# EFR32_IO.net
KiCad netlist of a schematic drawn in Altium Designer
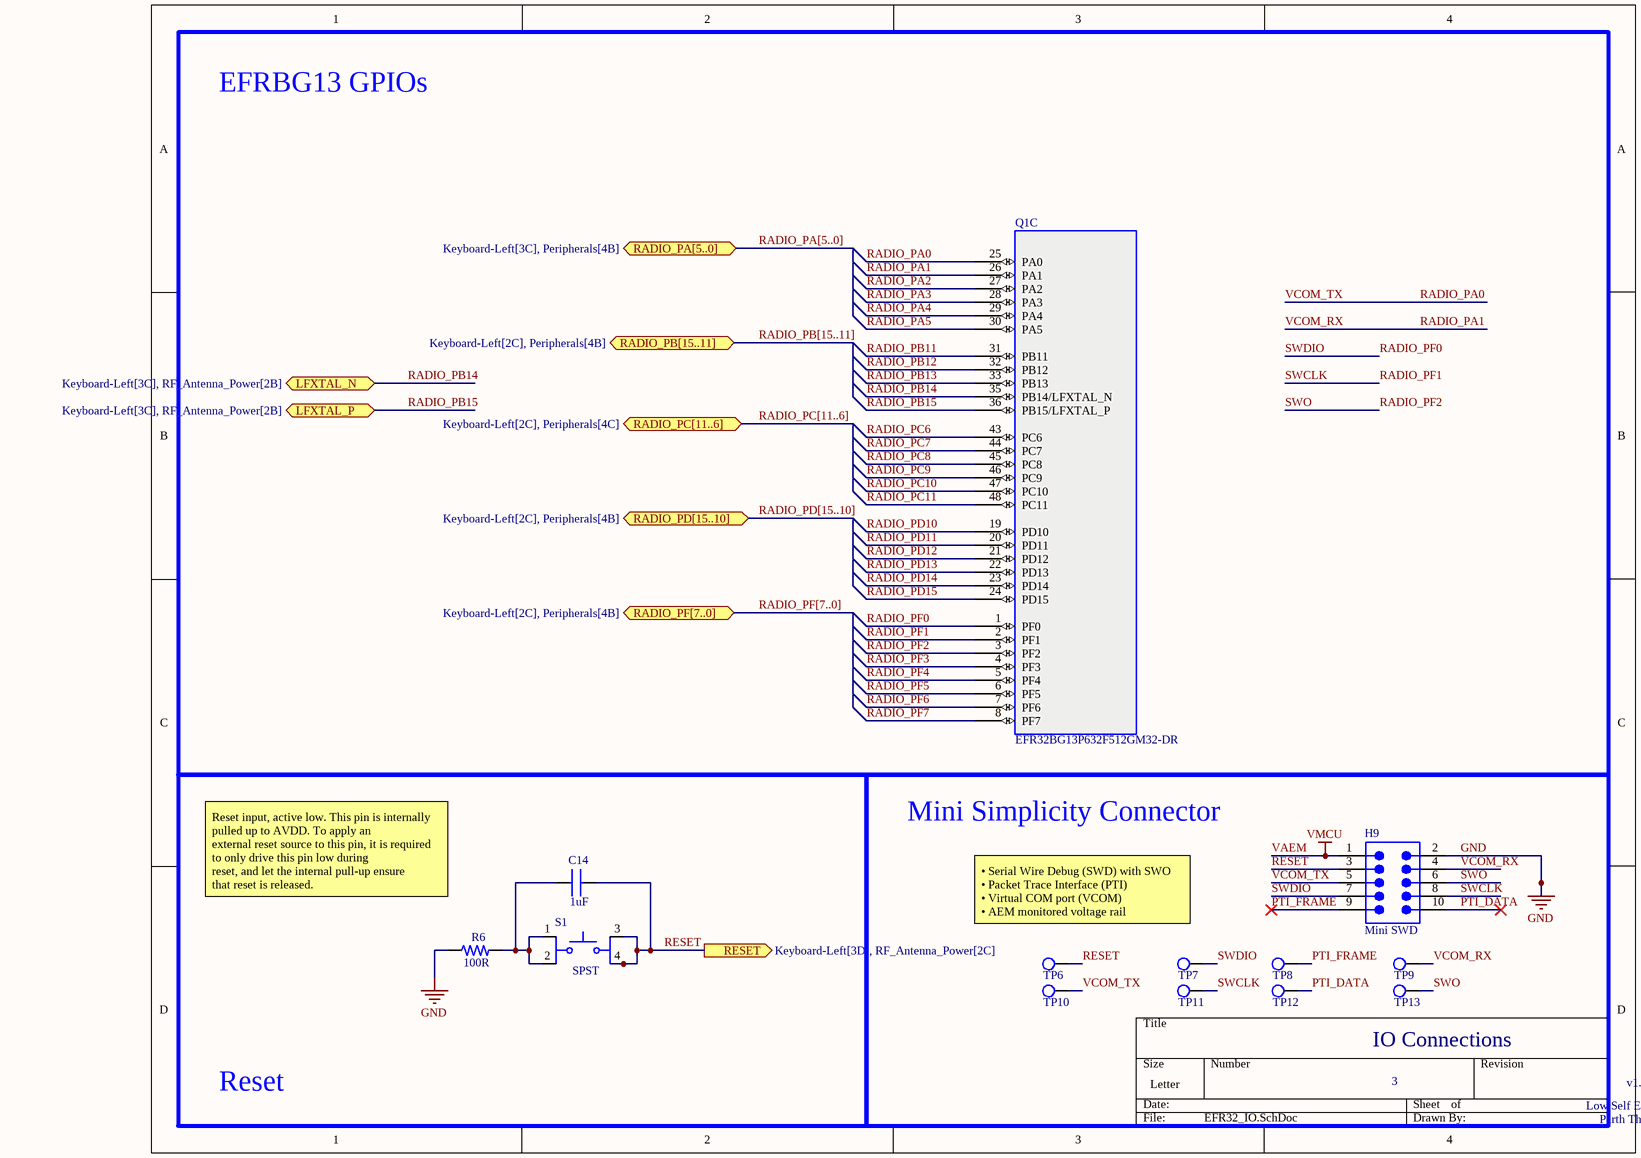
[diagram p0: EFR32_IO.SchDoc]

(export (version "E")
  (design (tool "Eeschema 10.0.6"))
  (components
    (comp (ref "C14")
      (value "1uF")
      (footprint "Capacitor 0603")
      (fields
        (field (name "MANUFACTURER") "Murata")
        (field (name "MANUFACTURER PART NUMBER") "GRM188R61A105KA61D")
        (field (name "Comment") "CAP 1uF 10V 0603")
      )
      (libsource (lib "Keyboard_parts") (part "CAP 1uF 10V 0603"))
    )
    (comp (ref "H9")
      (value "Mini SWD")
      (footprint "Mini Simplicity Connector")
      (description "Mini SWD 0.05\" Pitch Connector - 10 Pin SMT Box Header")
      (fields
        (field (name "MANUFACTURER") "Adafruit Industries")
        (field (name "MANUFACTURER PART NUMBER") "4048")
      )
      (libsource (lib "Keyboard_parts") (part "Debug Connector Mini SWD - 0.05{dblquote}"))
    )
    (comp (ref "Q1")
      (value "EFR32BG13P632F512GM32-DR")
      (footprint "EFR32BG")
      (description "BLue Gecko")
      (fields (field (name "MANUFACTURER") "Silicon Labs"))
      (libsource (lib "Keyboard_parts") (part "EFR32BG13P632F512GM32-DR"))
    )
    (comp (ref "R6")
      (value "100R")
      (footprint "Resistor 0603")
      (fields
        (field (name "MANUFACTURER") "Yageo")
        (field (name "MANUFACTURER PART NUMBER") "RC0603FR-07100RL")
        (field (name "TOLERANCE") "1%")
      )
      (libsource (lib "Keyboard_parts") (part "RES 100R 0603"))
    )
    (comp (ref "S1")
      (value "SPST")
      (footprint "SPST")
      (fields
        (field (name "MANUFACTURER") "E-Switch")
        (field (name "MANUFACTURER PART NUMBER") "TL3301NF260QG")
      )
      (libsource (lib "Keyboard_parts") (part "SPST"))
    )
    (comp (ref "TP6")
      (value "Test point")
      (footprint "Test Point")
      (libsource (lib "Keyboard_parts") (part "Test point"))
    )
    (comp (ref "TP7")
      (value "Test point")
      (footprint "Test Point")
      (libsource (lib "Keyboard_parts") (part "Test point"))
    )
    (comp (ref "TP8")
      (value "Test point")
      (footprint "Test Point")
      (libsource (lib "Keyboard_parts") (part "Test point"))
    )
    (comp (ref "TP9")
      (value "Test point")
      (footprint "Test Point")
      (libsource (lib "Keyboard_parts") (part "Test point"))
    )
    (comp (ref "TP10")
      (value "Test point")
      (footprint "Test Point")
      (libsource (lib "Keyboard_parts") (part "Test point"))
    )
    (comp (ref "TP11")
      (value "Test point")
      (footprint "Test Point")
      (libsource (lib "Keyboard_parts") (part "Test point"))
    )
    (comp (ref "TP12")
      (value "Test point")
      (footprint "Test Point")
      (libsource (lib "Keyboard_parts") (part "Test point"))
    )
    (comp (ref "TP13")
      (value "Test point")
      (footprint "Test Point")
      (libsource (lib "Keyboard_parts") (part "Test point"))
    )
  )
  (nets
    (net (code "1") (name "/PTI_DATA") (class "Default")
      (node (ref "H9") (pin "10") (pinfunction "10_10") (pintype "passive"))
      (node (ref "TP12") (pin "1") (pinfunction "1_1") (pintype "passive"))
    )
    (net (code "2") (name "/PTI_FRAME") (class "Default")
      (node (ref "H9") (pin "9") (pinfunction "9_9") (pintype "passive"))
      (node (ref "TP8") (pin "1") (pinfunction "1_1") (pintype "passive"))
    )
    (net (code "3") (name "/RADIO_PA0") (class "Default")
      (node (ref "H9") (pin "5") (pinfunction "5_5") (pintype "passive"))
      (node (ref "Q1") (pin "25") (pinfunction "PA0_25") (pintype "bidirectional"))
      (node (ref "TP10") (pin "1") (pinfunction "1_1") (pintype "passive"))
    )
    (net (code "4") (name "/RADIO_PA1") (class "Default")
      (node (ref "H9") (pin "4") (pinfunction "4_4") (pintype "passive"))
      (node (ref "Q1") (pin "26") (pinfunction "PA1_26") (pintype "bidirectional"))
      (node (ref "TP9") (pin "1") (pinfunction "1_1") (pintype "passive"))
    )
    (net (code "5") (name "/RADIO_PA2") (class "Default")
      (node (ref "Q1") (pin "27") (pinfunction "PA2_27") (pintype "bidirectional"))
    )
    (net (code "6") (name "/RADIO_PA3") (class "Default")
      (node (ref "Q1") (pin "28") (pinfunction "PA3_28") (pintype "bidirectional"))
    )
    (net (code "7") (name "/RADIO_PA4") (class "Default")
      (node (ref "Q1") (pin "29") (pinfunction "PA4_29") (pintype "bidirectional"))
    )
    (net (code "8") (name "/RADIO_PA5") (class "Default")
      (node (ref "Q1") (pin "30") (pinfunction "PA5_30") (pintype "bidirectional"))
    )
    (net (code "10") (name "/RADIO_PB11") (class "Default")
      (node (ref "Q1") (pin "31") (pinfunction "PB11_31") (pintype "bidirectional"))
    )
    (net (code "11") (name "/RADIO_PB12") (class "Default")
      (node (ref "Q1") (pin "32") (pinfunction "PB12_32") (pintype "bidirectional"))
    )
    (net (code "12") (name "/RADIO_PB13") (class "Default")
      (node (ref "Q1") (pin "33") (pinfunction "PB13_33") (pintype "bidirectional"))
    )
    (net (code "13") (name "/RADIO_PB14") (class "Default")
      (node (ref "Q1") (pin "35") (pinfunction "PB14/LFXTAL_N_35") (pintype "bidirectional"))
    )
    (net (code "14") (name "/RADIO_PB15") (class "Default")
      (node (ref "Q1") (pin "36") (pinfunction "PB15/LFXTAL_P_36") (pintype "bidirectional"))
    )
    (net (code "16") (name "/RADIO_PC6") (class "Default")
      (node (ref "Q1") (pin "43") (pinfunction "PC6_43") (pintype "bidirectional"))
    )
    (net (code "17") (name "/RADIO_PC7") (class "Default")
      (node (ref "Q1") (pin "44") (pinfunction "PC7_44") (pintype "bidirectional"))
    )
    (net (code "18") (name "/RADIO_PC8") (class "Default")
      (node (ref "Q1") (pin "45") (pinfunction "PC8_45") (pintype "bidirectional"))
    )
    (net (code "19") (name "/RADIO_PC9") (class "Default")
      (node (ref "Q1") (pin "46") (pinfunction "PC9_46") (pintype "bidirectional"))
    )
    (net (code "20") (name "/RADIO_PC10") (class "Default")
      (node (ref "Q1") (pin "47") (pinfunction "PC10_47") (pintype "bidirectional"))
    )
    (net (code "21") (name "/RADIO_PC11") (class "Default")
      (node (ref "Q1") (pin "48") (pinfunction "PC11_48") (pintype "bidirectional"))
    )
    (net (code "23") (name "/RADIO_PD10") (class "Default")
      (node (ref "Q1") (pin "19") (pinfunction "PD10_19") (pintype "bidirectional"))
    )
    (net (code "24") (name "/RADIO_PD11") (class "Default")
      (node (ref "Q1") (pin "20") (pinfunction "PD11_20") (pintype "bidirectional"))
    )
    (net (code "25") (name "/RADIO_PD12") (class "Default")
      (node (ref "Q1") (pin "21") (pinfunction "PD12_21") (pintype "bidirectional"))
    )
    (net (code "26") (name "/RADIO_PD13") (class "Default")
      (node (ref "Q1") (pin "22") (pinfunction "PD13_22") (pintype "bidirectional"))
    )
    (net (code "27") (name "/RADIO_PD14") (class "Default")
      (node (ref "Q1") (pin "23") (pinfunction "PD14_23") (pintype "bidirectional"))
    )
    (net (code "28") (name "/RADIO_PD15") (class "Default")
      (node (ref "Q1") (pin "24") (pinfunction "PD15_24") (pintype "bidirectional"))
    )
    (net (code "30") (name "/RADIO_PF0") (class "Default")
      (node (ref "H9") (pin "7") (pinfunction "7_7") (pintype "passive"))
      (node (ref "Q1") (pin "1") (pinfunction "PF0_1") (pintype "bidirectional"))
      (node (ref "TP7") (pin "1") (pinfunction "1_1") (pintype "passive"))
    )
    (net (code "31") (name "/RADIO_PF1") (class "Default")
      (node (ref "H9") (pin "8") (pinfunction "8_8") (pintype "passive"))
      (node (ref "Q1") (pin "2") (pinfunction "PF1_2") (pintype "bidirectional"))
      (node (ref "TP11") (pin "1") (pinfunction "1_1") (pintype "passive"))
    )
    (net (code "32") (name "/RADIO_PF2") (class "Default")
      (node (ref "H9") (pin "6") (pinfunction "6_6") (pintype "passive"))
      (node (ref "Q1") (pin "3") (pinfunction "PF2_3") (pintype "bidirectional"))
      (node (ref "TP13") (pin "1") (pinfunction "1_1") (pintype "passive"))
    )
    (net (code "33") (name "/RADIO_PF3") (class "Default")
      (node (ref "Q1") (pin "4") (pinfunction "PF3_4") (pintype "bidirectional"))
    )
    (net (code "34") (name "/RADIO_PF4") (class "Default")
      (node (ref "Q1") (pin "5") (pinfunction "PF4_5") (pintype "bidirectional"))
    )
    (net (code "35") (name "/RADIO_PF5") (class "Default")
      (node (ref "Q1") (pin "6") (pinfunction "PF5_6") (pintype "bidirectional"))
    )
    (net (code "36") (name "/RADIO_PF6") (class "Default")
      (node (ref "Q1") (pin "7") (pinfunction "PF6_7") (pintype "bidirectional"))
    )
    (net (code "37") (name "/RADIO_PF7") (class "Default")
      (node (ref "Q1") (pin "8") (pinfunction "PF7_8") (pintype "bidirectional"))
    )
    (net (code "39") (name "/RESET") (class "Default")
      (node (ref "C14") (pin "1") (pinfunction "1_1") (pintype "passive"))
      (node (ref "H9") (pin "3") (pinfunction "3_3") (pintype "passive"))
      (node (ref "S1") (pin "3") (pinfunction "3_3") (pintype "passive"))
      (node (ref "S1") (pin "4") (pinfunction "4_4") (pintype "passive"))
      (node (ref "TP6") (pin "1") (pinfunction "1_1") (pintype "passive"))
    )
    (net (code "40") (name "GND") (class "Default")
      (node (ref "H9") (pin "2") (pinfunction "2_2") (pintype "passive"))
      (node (ref "R6") (pin "1") (pinfunction "1_1") (pintype "passive"))
    )
    (net (code "41") (name "Net-(C14-Pad2)") (class "Default")
      (node (ref "C14") (pin "2") (pinfunction "2_2") (pintype "passive"))
      (node (ref "R6") (pin "2") (pinfunction "2_2") (pintype "passive"))
      (node (ref "S1") (pin "1") (pinfunction "1_1") (pintype "passive"))
      (node (ref "S1") (pin "2") (pinfunction "2_2") (pintype "passive"))
    )
    (net (code "42") (name "VMCU") (class "Default")
      (node (ref "H9") (pin "1") (pinfunction "1_1") (pintype "passive"))
    )
  )
)
